# in2-top.net
KiCad netlist of a schematic drawn in EAGLE
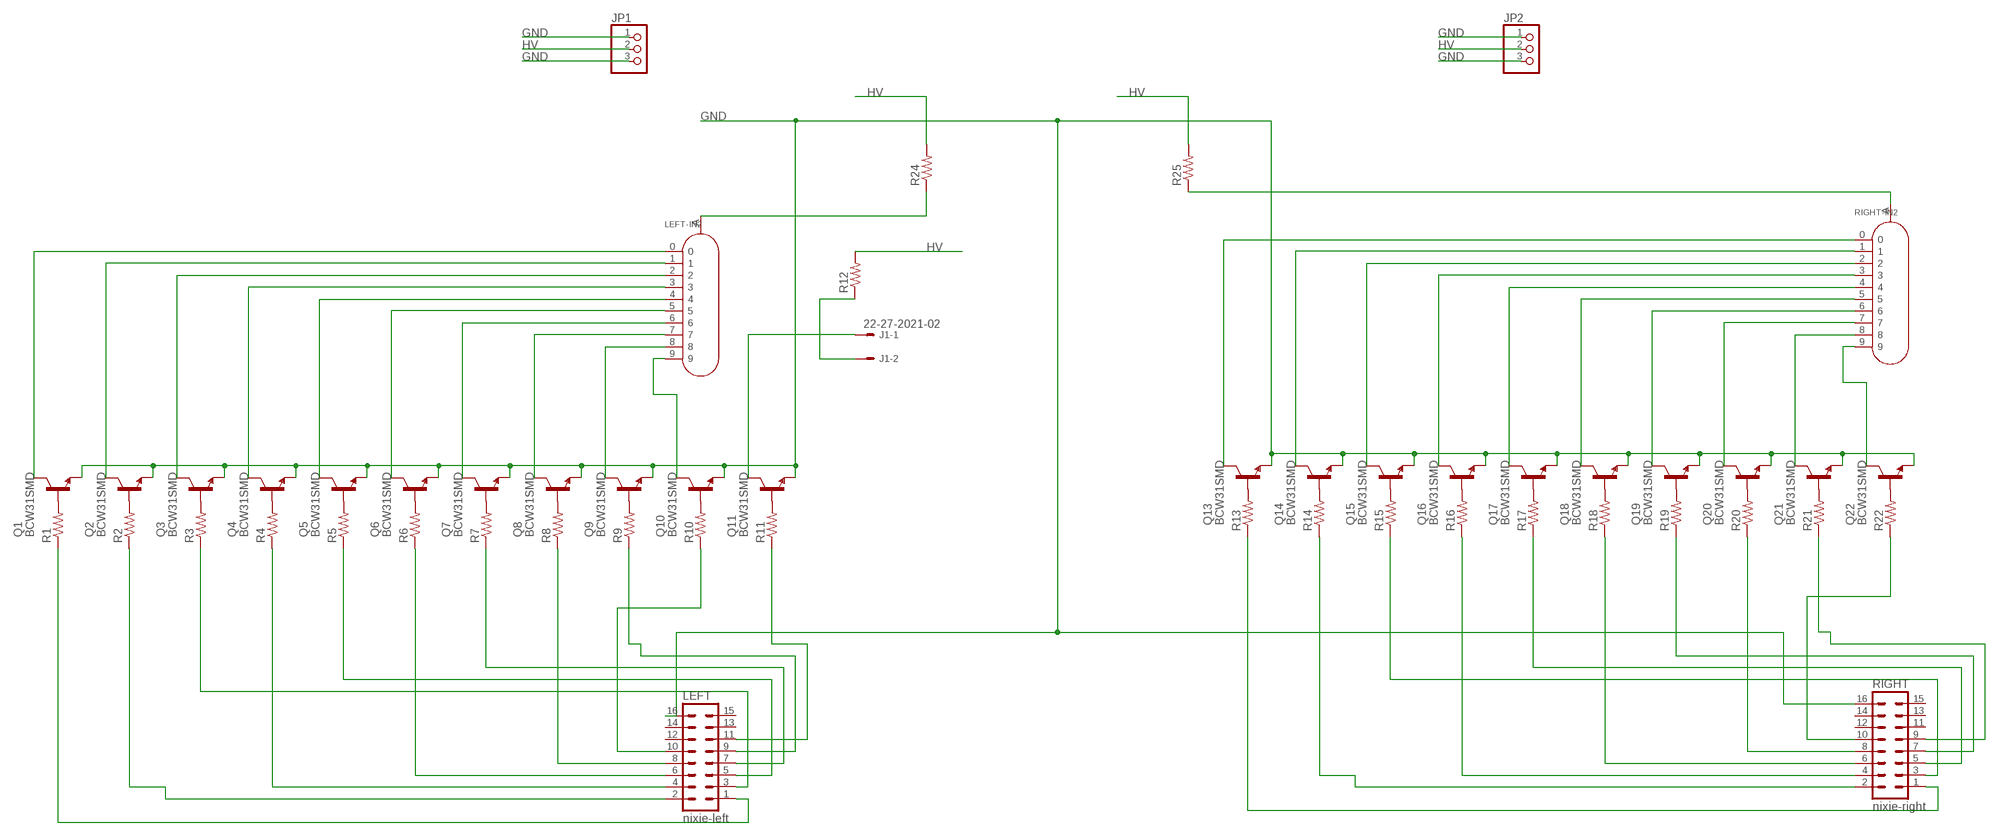
[diagram p0: schematic, sheet 1]

(export (version "E")
  (design (tool "Eeschema 10.0.6"))
  (components
    (comp (ref "J1")
      (value "22-27-2021-02")
      (footprint "eagle-import:6410-02")
      (libsource (lib "eagle-import") (part "22-?-0227-2021"))
    )
    (comp (ref "JP1")
      (value "PINHD-1X3")
      (footprint "eagle-import:1X03")
      (libsource (lib "eagle-import") (part "PINHD-1X3"))
    )
    (comp (ref "JP2")
      (value "PINHD-1X3")
      (footprint "eagle-import:1X03")
      (libsource (lib "eagle-import") (part "PINHD-1X3"))
    )
    (comp (ref "LEFT")
      (value "nixie-left")
      (footprint "eagle-import:ML16")
      (libsource (lib "eagle-import") (part "ML16"))
    )
    (comp (ref "LEFT-IN2")
      (value "IN-2")
      (footprint "eagle-import:IN-2")
      (libsource (lib "eagle-import") (part "IN-2"))
    )
    (comp (ref "Q1")
      (value "BCW31SMD")
      (footprint "eagle-import:SOT23-BEC")
      (libsource (lib "eagle-import") (part "BCW31SMD"))
    )
    (comp (ref "Q2")
      (value "BCW31SMD")
      (footprint "eagle-import:SOT23-BEC")
      (libsource (lib "eagle-import") (part "BCW31SMD"))
    )
    (comp (ref "Q3")
      (value "BCW31SMD")
      (footprint "eagle-import:SOT23-BEC")
      (libsource (lib "eagle-import") (part "BCW31SMD"))
    )
    (comp (ref "Q4")
      (value "BCW31SMD")
      (footprint "eagle-import:SOT23-BEC")
      (libsource (lib "eagle-import") (part "BCW31SMD"))
    )
    (comp (ref "Q5")
      (value "BCW31SMD")
      (footprint "eagle-import:SOT23-BEC")
      (libsource (lib "eagle-import") (part "BCW31SMD"))
    )
    (comp (ref "Q6")
      (value "BCW31SMD")
      (footprint "eagle-import:SOT23-BEC")
      (libsource (lib "eagle-import") (part "BCW31SMD"))
    )
    (comp (ref "Q7")
      (value "BCW31SMD")
      (footprint "eagle-import:SOT23-BEC")
      (libsource (lib "eagle-import") (part "BCW31SMD"))
    )
    (comp (ref "Q8")
      (value "BCW31SMD")
      (footprint "eagle-import:SOT23-BEC")
      (libsource (lib "eagle-import") (part "BCW31SMD"))
    )
    (comp (ref "Q9")
      (value "BCW31SMD")
      (footprint "eagle-import:SOT23-BEC")
      (libsource (lib "eagle-import") (part "BCW31SMD"))
    )
    (comp (ref "Q10")
      (value "BCW31SMD")
      (footprint "eagle-import:SOT23-BEC")
      (libsource (lib "eagle-import") (part "BCW31SMD"))
    )
    (comp (ref "Q11")
      (value "BCW31SMD")
      (footprint "eagle-import:SOT23-BEC")
      (libsource (lib "eagle-import") (part "BCW31SMD"))
    )
    (comp (ref "Q13")
      (value "BCW31SMD")
      (footprint "eagle-import:SOT23-BEC")
      (libsource (lib "eagle-import") (part "BCW31SMD"))
    )
    (comp (ref "Q14")
      (value "BCW31SMD")
      (footprint "eagle-import:SOT23-BEC")
      (libsource (lib "eagle-import") (part "BCW31SMD"))
    )
    (comp (ref "Q15")
      (value "BCW31SMD")
      (footprint "eagle-import:SOT23-BEC")
      (libsource (lib "eagle-import") (part "BCW31SMD"))
    )
    (comp (ref "Q16")
      (value "BCW31SMD")
      (footprint "eagle-import:SOT23-BEC")
      (libsource (lib "eagle-import") (part "BCW31SMD"))
    )
    (comp (ref "Q17")
      (value "BCW31SMD")
      (footprint "eagle-import:SOT23-BEC")
      (libsource (lib "eagle-import") (part "BCW31SMD"))
    )
    (comp (ref "Q18")
      (value "BCW31SMD")
      (footprint "eagle-import:SOT23-BEC")
      (libsource (lib "eagle-import") (part "BCW31SMD"))
    )
    (comp (ref "Q19")
      (value "BCW31SMD")
      (footprint "eagle-import:SOT23-BEC")
      (libsource (lib "eagle-import") (part "BCW31SMD"))
    )
    (comp (ref "Q20")
      (value "BCW31SMD")
      (footprint "eagle-import:SOT23-BEC")
      (libsource (lib "eagle-import") (part "BCW31SMD"))
    )
    (comp (ref "Q21")
      (value "BCW31SMD")
      (footprint "eagle-import:SOT23-BEC")
      (libsource (lib "eagle-import") (part "BCW31SMD"))
    )
    (comp (ref "Q22")
      (value "BCW31SMD")
      (footprint "eagle-import:SOT23-BEC")
      (libsource (lib "eagle-import") (part "BCW31SMD"))
    )
    (comp (ref "R1")
      (value "R-US_M0805")
      (footprint "eagle-import:M0805")
      (libsource (lib "eagle-import") (part "R-US_M0805"))
    )
    (comp (ref "R2")
      (value "R-US_M0805")
      (footprint "eagle-import:M0805")
      (libsource (lib "eagle-import") (part "R-US_M0805"))
    )
    (comp (ref "R3")
      (value "R-US_M0805")
      (footprint "eagle-import:M0805")
      (libsource (lib "eagle-import") (part "R-US_M0805"))
    )
    (comp (ref "R4")
      (value "R-US_M0805")
      (footprint "eagle-import:M0805")
      (libsource (lib "eagle-import") (part "R-US_M0805"))
    )
    (comp (ref "R5")
      (value "R-US_M0805")
      (footprint "eagle-import:M0805")
      (libsource (lib "eagle-import") (part "R-US_M0805"))
    )
    (comp (ref "R6")
      (value "R-US_M0805")
      (footprint "eagle-import:M0805")
      (libsource (lib "eagle-import") (part "R-US_M0805"))
    )
    (comp (ref "R7")
      (value "R-US_M0805")
      (footprint "eagle-import:M0805")
      (libsource (lib "eagle-import") (part "R-US_M0805"))
    )
    (comp (ref "R8")
      (value "R-US_M0805")
      (footprint "eagle-import:M0805")
      (libsource (lib "eagle-import") (part "R-US_M0805"))
    )
    (comp (ref "R9")
      (value "R-US_M0805")
      (footprint "eagle-import:M0805")
      (libsource (lib "eagle-import") (part "R-US_M0805"))
    )
    (comp (ref "R10")
      (value "R-US_M0805")
      (footprint "eagle-import:M0805")
      (libsource (lib "eagle-import") (part "R-US_M0805"))
    )
    (comp (ref "R11")
      (value "R-US_M0805")
      (footprint "eagle-import:M0805")
      (libsource (lib "eagle-import") (part "R-US_M0805"))
    )
    (comp (ref "R12")
      (value "R-US_R0805")
      (footprint "eagle-import:R0805")
      (libsource (lib "eagle-import") (part "R-US_R0805"))
    )
    (comp (ref "R13")
      (value "R-US_M0805")
      (footprint "eagle-import:M0805")
      (libsource (lib "eagle-import") (part "R-US_M0805"))
    )
    (comp (ref "R14")
      (value "R-US_M0805")
      (footprint "eagle-import:M0805")
      (libsource (lib "eagle-import") (part "R-US_M0805"))
    )
    (comp (ref "R15")
      (value "R-US_M0805")
      (footprint "eagle-import:M0805")
      (libsource (lib "eagle-import") (part "R-US_M0805"))
    )
    (comp (ref "R16")
      (value "R-US_M0805")
      (footprint "eagle-import:M0805")
      (libsource (lib "eagle-import") (part "R-US_M0805"))
    )
    (comp (ref "R17")
      (value "R-US_M0805")
      (footprint "eagle-import:M0805")
      (libsource (lib "eagle-import") (part "R-US_M0805"))
    )
    (comp (ref "R18")
      (value "R-US_M0805")
      (footprint "eagle-import:M0805")
      (libsource (lib "eagle-import") (part "R-US_M0805"))
    )
    (comp (ref "R19")
      (value "R-US_M0805")
      (footprint "eagle-import:M0805")
      (libsource (lib "eagle-import") (part "R-US_M0805"))
    )
    (comp (ref "R20")
      (value "R-US_M0805")
      (footprint "eagle-import:M0805")
      (libsource (lib "eagle-import") (part "R-US_M0805"))
    )
    (comp (ref "R21")
      (value "R-US_M0805")
      (footprint "eagle-import:M0805")
      (libsource (lib "eagle-import") (part "R-US_M0805"))
    )
    (comp (ref "R22")
      (value "R-US_M0805")
      (footprint "eagle-import:M0805")
      (libsource (lib "eagle-import") (part "R-US_M0805"))
    )
    (comp (ref "R24")
      (value "R-US_R0805")
      (footprint "eagle-import:R0805")
      (libsource (lib "eagle-import") (part "R-US_R0805"))
    )
    (comp (ref "R25")
      (value "R-US_R0805")
      (footprint "eagle-import:R0805")
      (libsource (lib "eagle-import") (part "R-US_R0805"))
    )
    (comp (ref "RIGHT")
      (value "nixie-right")
      (footprint "eagle-import:ML16")
      (libsource (lib "eagle-import") (part "ML16"))
    )
    (comp (ref "RIGHT-IN2")
      (value "IN-2")
      (footprint "eagle-import:IN-2")
      (libsource (lib "eagle-import") (part "IN-2"))
    )
  )
  (nets
    (net (code "1") (name "/GND") (class "Default")
      (node (ref "JP1") (pin "1") (pinfunction "1_1") (pintype "passive"))
      (node (ref "JP1") (pin "3") (pinfunction "3_3") (pintype "passive"))
      (node (ref "JP2") (pin "1") (pinfunction "1_1") (pintype "passive"))
      (node (ref "JP2") (pin "3") (pinfunction "3_3") (pintype "passive"))
      (node (ref "LEFT") (pin "16") (pinfunction "16_16") (pintype "passive"))
      (node (ref "Q1") (pin "E") (pinfunction "E_E") (pintype "passive"))
      (node (ref "Q10") (pin "E") (pinfunction "E_E") (pintype "passive"))
      (node (ref "Q11") (pin "E") (pinfunction "E_E") (pintype "passive"))
      (node (ref "Q13") (pin "E") (pinfunction "E_E") (pintype "passive"))
      (node (ref "Q14") (pin "E") (pinfunction "E_E") (pintype "passive"))
      (node (ref "Q15") (pin "E") (pinfunction "E_E") (pintype "passive"))
      (node (ref "Q16") (pin "E") (pinfunction "E_E") (pintype "passive"))
      (node (ref "Q17") (pin "E") (pinfunction "E_E") (pintype "passive"))
      (node (ref "Q18") (pin "E") (pinfunction "E_E") (pintype "passive"))
      (node (ref "Q19") (pin "E") (pinfunction "E_E") (pintype "passive"))
      (node (ref "Q2") (pin "E") (pinfunction "E_E") (pintype "passive"))
      (node (ref "Q20") (pin "E") (pinfunction "E_E") (pintype "passive"))
      (node (ref "Q21") (pin "E") (pinfunction "E_E") (pintype "passive"))
      (node (ref "Q22") (pin "E") (pinfunction "E_E") (pintype "passive"))
      (node (ref "Q3") (pin "E") (pinfunction "E_E") (pintype "passive"))
      (node (ref "Q4") (pin "E") (pinfunction "E_E") (pintype "passive"))
      (node (ref "Q5") (pin "E") (pinfunction "E_E") (pintype "passive"))
      (node (ref "Q6") (pin "E") (pinfunction "E_E") (pintype "passive"))
      (node (ref "Q7") (pin "E") (pinfunction "E_E") (pintype "passive"))
      (node (ref "Q8") (pin "E") (pinfunction "E_E") (pintype "passive"))
      (node (ref "Q9") (pin "E") (pinfunction "E_E") (pintype "passive"))
      (node (ref "RIGHT") (pin "16") (pinfunction "16_16") (pintype "passive"))
    )
    (net (code "2") (name "/HV") (class "Default")
      (node (ref "JP1") (pin "2") (pinfunction "2_2") (pintype "passive"))
      (node (ref "JP2") (pin "2") (pinfunction "2_2") (pintype "passive"))
      (node (ref "R12") (pin "2") (pinfunction "2_2") (pintype "passive"))
      (node (ref "R24") (pin "2") (pinfunction "2_2") (pintype "passive"))
      (node (ref "R25") (pin "2") (pinfunction "2_2") (pintype "passive"))
    )
    (net (code "3") (name "Net-(J1A-S)") (class "Default")
      (node (ref "J1") (pin "1") (pinfunction "S_1") (pintype "passive"))
      (node (ref "Q11") (pin "C") (pinfunction "C_C") (pintype "passive"))
    )
    (net (code "4") (name "Net-(J1B-S)") (class "Default")
      (node (ref "J1") (pin "2") (pinfunction "S_2") (pintype "passive"))
      (node (ref "R12") (pin "1") (pinfunction "1_1") (pintype "passive"))
    )
    (net (code "5") (name "Net-(LEFT-IN2-Pad0)") (class "Default")
      (node (ref "LEFT-IN2") (pin "0") (pinfunction "0_0") (pintype "bidirectional"))
      (node (ref "Q1") (pin "C") (pinfunction "C_C") (pintype "passive"))
    )
    (net (code "6") (name "Net-(LEFT-IN2-Pad1)") (class "Default")
      (node (ref "LEFT-IN2") (pin "1") (pinfunction "1_1") (pintype "bidirectional"))
      (node (ref "Q2") (pin "C") (pinfunction "C_C") (pintype "passive"))
    )
    (net (code "7") (name "Net-(LEFT-IN2-Pad2)") (class "Default")
      (node (ref "LEFT-IN2") (pin "2") (pinfunction "2_2") (pintype "bidirectional"))
      (node (ref "Q3") (pin "C") (pinfunction "C_C") (pintype "passive"))
    )
    (net (code "8") (name "Net-(LEFT-IN2-Pad3)") (class "Default")
      (node (ref "LEFT-IN2") (pin "3") (pinfunction "3_3") (pintype "bidirectional"))
      (node (ref "Q4") (pin "C") (pinfunction "C_C") (pintype "passive"))
    )
    (net (code "9") (name "Net-(LEFT-IN2-Pad4)") (class "Default")
      (node (ref "LEFT-IN2") (pin "4") (pinfunction "4_4") (pintype "bidirectional"))
      (node (ref "Q5") (pin "C") (pinfunction "C_C") (pintype "passive"))
    )
    (net (code "10") (name "Net-(LEFT-IN2-Pad5)") (class "Default")
      (node (ref "LEFT-IN2") (pin "5") (pinfunction "5_5") (pintype "bidirectional"))
      (node (ref "Q6") (pin "C") (pinfunction "C_C") (pintype "passive"))
    )
    (net (code "11") (name "Net-(LEFT-IN2-Pad6)") (class "Default")
      (node (ref "LEFT-IN2") (pin "6") (pinfunction "6_6") (pintype "bidirectional"))
      (node (ref "Q7") (pin "C") (pinfunction "C_C") (pintype "passive"))
    )
    (net (code "12") (name "Net-(LEFT-IN2-Pad7)") (class "Default")
      (node (ref "LEFT-IN2") (pin "7") (pinfunction "7_7") (pintype "bidirectional"))
      (node (ref "Q8") (pin "C") (pinfunction "C_C") (pintype "passive"))
    )
    (net (code "13") (name "Net-(LEFT-IN2-Pad8)") (class "Default")
      (node (ref "LEFT-IN2") (pin "8") (pinfunction "8_8") (pintype "bidirectional"))
      (node (ref "Q9") (pin "C") (pinfunction "C_C") (pintype "passive"))
    )
    (net (code "14") (name "Net-(LEFT-IN2-Pad9)") (class "Default")
      (node (ref "LEFT-IN2") (pin "9") (pinfunction "9_9") (pintype "bidirectional"))
      (node (ref "Q10") (pin "C") (pinfunction "C_C") (pintype "passive"))
    )
    (net (code "15") (name "Net-(LEFT-IN2-PadA)") (class "Default")
      (node (ref "LEFT-IN2") (pin "A") (pinfunction "A_A") (pintype "bidirectional"))
      (node (ref "R24") (pin "1") (pinfunction "1_1") (pintype "passive"))
    )
    (net (code "16") (name "Net-(LEFT-Pad1)") (class "Default")
      (node (ref "LEFT") (pin "1") (pinfunction "1_1") (pintype "passive"))
      (node (ref "R1") (pin "1") (pinfunction "1_1") (pintype "passive"))
    )
    (net (code "17") (name "Net-(LEFT-Pad2)") (class "Default")
      (node (ref "LEFT") (pin "2") (pinfunction "2_2") (pintype "passive"))
      (node (ref "R2") (pin "1") (pinfunction "1_1") (pintype "passive"))
    )
    (net (code "18") (name "Net-(LEFT-Pad3)") (class "Default")
      (node (ref "LEFT") (pin "3") (pinfunction "3_3") (pintype "passive"))
      (node (ref "R3") (pin "1") (pinfunction "1_1") (pintype "passive"))
    )
    (net (code "19") (name "Net-(LEFT-Pad4)") (class "Default")
      (node (ref "LEFT") (pin "4") (pinfunction "4_4") (pintype "passive"))
      (node (ref "R4") (pin "1") (pinfunction "1_1") (pintype "passive"))
    )
    (net (code "20") (name "Net-(LEFT-Pad5)") (class "Default")
      (node (ref "LEFT") (pin "5") (pinfunction "5_5") (pintype "passive"))
      (node (ref "R5") (pin "1") (pinfunction "1_1") (pintype "passive"))
    )
    (net (code "21") (name "Net-(LEFT-Pad6)") (class "Default")
      (node (ref "LEFT") (pin "6") (pinfunction "6_6") (pintype "passive"))
      (node (ref "R6") (pin "1") (pinfunction "1_1") (pintype "passive"))
    )
    (net (code "22") (name "Net-(LEFT-Pad7)") (class "Default")
      (node (ref "LEFT") (pin "7") (pinfunction "7_7") (pintype "passive"))
      (node (ref "R7") (pin "1") (pinfunction "1_1") (pintype "passive"))
    )
    (net (code "23") (name "Net-(LEFT-Pad8)") (class "Default")
      (node (ref "LEFT") (pin "8") (pinfunction "8_8") (pintype "passive"))
      (node (ref "R8") (pin "1") (pinfunction "1_1") (pintype "passive"))
    )
    (net (code "24") (name "Net-(LEFT-Pad9)") (class "Default")
      (node (ref "LEFT") (pin "9") (pinfunction "9_9") (pintype "passive"))
      (node (ref "R9") (pin "1") (pinfunction "1_1") (pintype "passive"))
    )
    (net (code "25") (name "Net-(LEFT-Pad10)") (class "Default")
      (node (ref "LEFT") (pin "10") (pinfunction "10_10") (pintype "passive"))
      (node (ref "R10") (pin "1") (pinfunction "1_1") (pintype "passive"))
    )
    (net (code "26") (name "Net-(LEFT-Pad11)") (class "Default")
      (node (ref "LEFT") (pin "11") (pinfunction "11_11") (pintype "passive"))
      (node (ref "R11") (pin "1") (pinfunction "1_1") (pintype "passive"))
    )
    (net (code "27") (name "Net-(Q1-PadB)") (class "Default")
      (node (ref "Q1") (pin "B") (pinfunction "B_B") (pintype "passive"))
      (node (ref "R1") (pin "2") (pinfunction "2_2") (pintype "passive"))
    )
    (net (code "28") (name "Net-(Q2-PadB)") (class "Default")
      (node (ref "Q2") (pin "B") (pinfunction "B_B") (pintype "passive"))
      (node (ref "R2") (pin "2") (pinfunction "2_2") (pintype "passive"))
    )
    (net (code "29") (name "Net-(Q3-PadB)") (class "Default")
      (node (ref "Q3") (pin "B") (pinfunction "B_B") (pintype "passive"))
      (node (ref "R3") (pin "2") (pinfunction "2_2") (pintype "passive"))
    )
    (net (code "30") (name "Net-(Q4-PadB)") (class "Default")
      (node (ref "Q4") (pin "B") (pinfunction "B_B") (pintype "passive"))
      (node (ref "R4") (pin "2") (pinfunction "2_2") (pintype "passive"))
    )
    (net (code "31") (name "Net-(Q5-PadB)") (class "Default")
      (node (ref "Q5") (pin "B") (pinfunction "B_B") (pintype "passive"))
      (node (ref "R5") (pin "2") (pinfunction "2_2") (pintype "passive"))
    )
    (net (code "32") (name "Net-(Q6-PadB)") (class "Default")
      (node (ref "Q6") (pin "B") (pinfunction "B_B") (pintype "passive"))
      (node (ref "R6") (pin "2") (pinfunction "2_2") (pintype "passive"))
    )
    (net (code "33") (name "Net-(Q7-PadB)") (class "Default")
      (node (ref "Q7") (pin "B") (pinfunction "B_B") (pintype "passive"))
      (node (ref "R7") (pin "2") (pinfunction "2_2") (pintype "passive"))
    )
    (net (code "34") (name "Net-(Q8-PadB)") (class "Default")
      (node (ref "Q8") (pin "B") (pinfunction "B_B") (pintype "passive"))
      (node (ref "R8") (pin "2") (pinfunction "2_2") (pintype "passive"))
    )
    (net (code "35") (name "Net-(Q9-PadB)") (class "Default")
      (node (ref "Q9") (pin "B") (pinfunction "B_B") (pintype "passive"))
      (node (ref "R9") (pin "2") (pinfunction "2_2") (pintype "passive"))
    )
    (net (code "36") (name "Net-(Q10-PadB)") (class "Default")
      (node (ref "Q10") (pin "B") (pinfunction "B_B") (pintype "passive"))
      (node (ref "R10") (pin "2") (pinfunction "2_2") (pintype "passive"))
    )
    (net (code "37") (name "Net-(Q11-PadB)") (class "Default")
      (node (ref "Q11") (pin "B") (pinfunction "B_B") (pintype "passive"))
      (node (ref "R11") (pin "2") (pinfunction "2_2") (pintype "passive"))
    )
    (net (code "38") (name "Net-(Q13-PadB)") (class "Default")
      (node (ref "Q13") (pin "B") (pinfunction "B_B") (pintype "passive"))
      (node (ref "R13") (pin "2") (pinfunction "2_2") (pintype "passive"))
    )
    (net (code "39") (name "Net-(Q13-PadC)") (class "Default")
      (node (ref "Q13") (pin "C") (pinfunction "C_C") (pintype "passive"))
      (node (ref "RIGHT-IN2") (pin "0") (pinfunction "0_0") (pintype "bidirectional"))
    )
    (net (code "40") (name "Net-(Q14-PadB)") (class "Default")
      (node (ref "Q14") (pin "B") (pinfunction "B_B") (pintype "passive"))
      (node (ref "R14") (pin "2") (pinfunction "2_2") (pintype "passive"))
    )
    (net (code "41") (name "Net-(Q14-PadC)") (class "Default")
      (node (ref "Q14") (pin "C") (pinfunction "C_C") (pintype "passive"))
      (node (ref "RIGHT-IN2") (pin "1") (pinfunction "1_1") (pintype "bidirectional"))
    )
    (net (code "42") (name "Net-(Q15-PadB)") (class "Default")
      (node (ref "Q15") (pin "B") (pinfunction "B_B") (pintype "passive"))
      (node (ref "R15") (pin "2") (pinfunction "2_2") (pintype "passive"))
    )
    (net (code "43") (name "Net-(Q15-PadC)") (class "Default")
      (node (ref "Q15") (pin "C") (pinfunction "C_C") (pintype "passive"))
      (node (ref "RIGHT-IN2") (pin "2") (pinfunction "2_2") (pintype "bidirectional"))
    )
    (net (code "44") (name "Net-(Q16-PadB)") (class "Default")
      (node (ref "Q16") (pin "B") (pinfunction "B_B") (pintype "passive"))
      (node (ref "R16") (pin "2") (pinfunction "2_2") (pintype "passive"))
    )
    (net (code "45") (name "Net-(Q16-PadC)") (class "Default")
      (node (ref "Q16") (pin "C") (pinfunction "C_C") (pintype "passive"))
      (node (ref "RIGHT-IN2") (pin "3") (pinfunction "3_3") (pintype "bidirectional"))
    )
    (net (code "46") (name "Net-(Q17-PadB)") (class "Default")
      (node (ref "Q17") (pin "B") (pinfunction "B_B") (pintype "passive"))
      (node (ref "R17") (pin "2") (pinfunction "2_2") (pintype "passive"))
    )
    (net (code "47") (name "Net-(Q17-PadC)") (class "Default")
      (node (ref "Q17") (pin "C") (pinfunction "C_C") (pintype "passive"))
      (node (ref "RIGHT-IN2") (pin "4") (pinfunction "4_4") (pintype "bidirectional"))
    )
    (net (code "48") (name "Net-(Q18-PadB)") (class "Default")
      (node (ref "Q18") (pin "B") (pinfunction "B_B") (pintype "passive"))
      (node (ref "R18") (pin "2") (pinfunction "2_2") (pintype "passive"))
    )
    (net (code "49") (name "Net-(Q18-PadC)") (class "Default")
      (node (ref "Q18") (pin "C") (pinfunction "C_C") (pintype "passive"))
      (node (ref "RIGHT-IN2") (pin "5") (pinfunction "5_5") (pintype "bidirectional"))
    )
    (net (code "50") (name "Net-(Q19-PadB)") (class "Default")
      (node (ref "Q19") (pin "B") (pinfunction "B_B") (pintype "passive"))
      (node (ref "R19") (pin "2") (pinfunction "2_2") (pintype "passive"))
    )
    (net (code "51") (name "Net-(Q19-PadC)") (class "Default")
      (node (ref "Q19") (pin "C") (pinfunction "C_C") (pintype "passive"))
      (node (ref "RIGHT-IN2") (pin "6") (pinfunction "6_6") (pintype "bidirectional"))
    )
    (net (code "52") (name "Net-(Q20-PadB)") (class "Default")
      (node (ref "Q20") (pin "B") (pinfunction "B_B") (pintype "passive"))
      (node (ref "R20") (pin "2") (pinfunction "2_2") (pintype "passive"))
    )
    (net (code "53") (name "Net-(Q20-PadC)") (class "Default")
      (node (ref "Q20") (pin "C") (pinfunction "C_C") (pintype "passive"))
      (node (ref "RIGHT-IN2") (pin "7") (pinfunction "7_7") (pintype "bidirectional"))
    )
    (net (code "54") (name "Net-(Q21-PadB)") (class "Default")
      (node (ref "Q21") (pin "B") (pinfunction "B_B") (pintype "passive"))
      (node (ref "R21") (pin "2") (pinfunction "2_2") (pintype "passive"))
    )
    (net (code "55") (name "Net-(Q21-PadC)") (class "Default")
      (node (ref "Q21") (pin "C") (pinfunction "C_C") (pintype "passive"))
      (node (ref "RIGHT-IN2") (pin "8") (pinfunction "8_8") (pintype "bidirectional"))
    )
    (net (code "56") (name "Net-(Q22-PadB)") (class "Default")
      (node (ref "Q22") (pin "B") (pinfunction "B_B") (pintype "passive"))
      (node (ref "R22") (pin "2") (pinfunction "2_2") (pintype "passive"))
    )
    (net (code "57") (name "Net-(Q22-PadC)") (class "Default")
      (node (ref "Q22") (pin "C") (pinfunction "C_C") (pintype "passive"))
      (node (ref "RIGHT-IN2") (pin "9") (pinfunction "9_9") (pintype "bidirectional"))
    )
    (net (code "58") (name "Net-(R13-Pad1)") (class "Default")
      (node (ref "R13") (pin "1") (pinfunction "1_1") (pintype "passive"))
      (node (ref "RIGHT") (pin "1") (pinfunction "1_1") (pintype "passive"))
    )
    (net (code "59") (name "Net-(R14-Pad1)") (class "Default")
      (node (ref "R14") (pin "1") (pinfunction "1_1") (pintype "passive"))
      (node (ref "RIGHT") (pin "2") (pinfunction "2_2") (pintype "passive"))
    )
    (net (code "60") (name "Net-(R15-Pad1)") (class "Default")
      (node (ref "R15") (pin "1") (pinfunction "1_1") (pintype "passive"))
      (node (ref "RIGHT") (pin "3") (pinfunction "3_3") (pintype "passive"))
    )
    (net (code "61") (name "Net-(R16-Pad1)") (class "Default")
      (node (ref "R16") (pin "1") (pinfunction "1_1") (pintype "passive"))
      (node (ref "RIGHT") (pin "4") (pinfunction "4_4") (pintype "passive"))
    )
    (net (code "62") (name "Net-(R17-Pad1)") (class "Default")
      (node (ref "R17") (pin "1") (pinfunction "1_1") (pintype "passive"))
      (node (ref "RIGHT") (pin "5") (pinfunction "5_5") (pintype "passive"))
    )
    (net (code "63") (name "Net-(R18-Pad1)") (class "Default")
      (node (ref "R18") (pin "1") (pinfunction "1_1") (pintype "passive"))
      (node (ref "RIGHT") (pin "6") (pinfunction "6_6") (pintype "passive"))
    )
    (net (code "64") (name "Net-(R19-Pad1)") (class "Default")
      (node (ref "R19") (pin "1") (pinfunction "1_1") (pintype "passive"))
      (node (ref "RIGHT") (pin "7") (pinfunction "7_7") (pintype "passive"))
    )
    (net (code "65") (name "Net-(R20-Pad1)") (class "Default")
      (node (ref "R20") (pin "1") (pinfunction "1_1") (pintype "passive"))
      (node (ref "RIGHT") (pin "8") (pinfunction "8_8") (pintype "passive"))
    )
    (net (code "66") (name "Net-(R21-Pad1)") (class "Default")
      (node (ref "R21") (pin "1") (pinfunction "1_1") (pintype "passive"))
      (node (ref "RIGHT") (pin "9") (pinfunction "9_9") (pintype "passive"))
    )
    (net (code "67") (name "Net-(R22-Pad1)") (class "Default")
      (node (ref "R22") (pin "1") (pinfunction "1_1") (pintype "passive"))
      (node (ref "RIGHT") (pin "10") (pinfunction "10_10") (pintype "passive"))
    )
    (net (code "68") (name "Net-(R25-Pad1)") (class "Default")
      (node (ref "R25") (pin "1") (pinfunction "1_1") (pintype "passive"))
      (node (ref "RIGHT-IN2") (pin "A") (pinfunction "A_A") (pintype "bidirectional"))
    )
    (net (code "69") (name "unconnected-(LEFT-Pad12)") (class "Default")
      (node (ref "LEFT") (pin "12") (pinfunction "12_12") (pintype "passive"))
    )
    (net (code "70") (name "unconnected-(LEFT-Pad13)") (class "Default")
      (node (ref "LEFT") (pin "13") (pinfunction "13_13") (pintype "passive"))
    )
    (net (code "71") (name "unconnected-(LEFT-Pad14)") (class "Default")
      (node (ref "LEFT") (pin "14") (pinfunction "14_14") (pintype "passive"))
    )
    (net (code "72") (name "unconnected-(LEFT-Pad15)") (class "Default")
      (node (ref "LEFT") (pin "15") (pinfunction "15_15") (pintype "passive"))
    )
    (net (code "73") (name "unconnected-(RIGHT-Pad11)") (class "Default")
      (node (ref "RIGHT") (pin "11") (pinfunction "11_11") (pintype "passive"))
    )
    (net (code "74") (name "unconnected-(RIGHT-Pad12)") (class "Default")
      (node (ref "RIGHT") (pin "12") (pinfunction "12_12") (pintype "passive"))
    )
    (net (code "75") (name "unconnected-(RIGHT-Pad13)") (class "Default")
      (node (ref "RIGHT") (pin "13") (pinfunction "13_13") (pintype "passive"))
    )
    (net (code "76") (name "unconnected-(RIGHT-Pad14)") (class "Default")
      (node (ref "RIGHT") (pin "14") (pinfunction "14_14") (pintype "passive"))
    )
    (net (code "77") (name "unconnected-(RIGHT-Pad15)") (class "Default")
      (node (ref "RIGHT") (pin "15") (pinfunction "15_15") (pintype "passive"))
    )
  )
)
